# MINI_SAM_D51_019.net
KiCad netlist of a schematic drawn in EAGLE
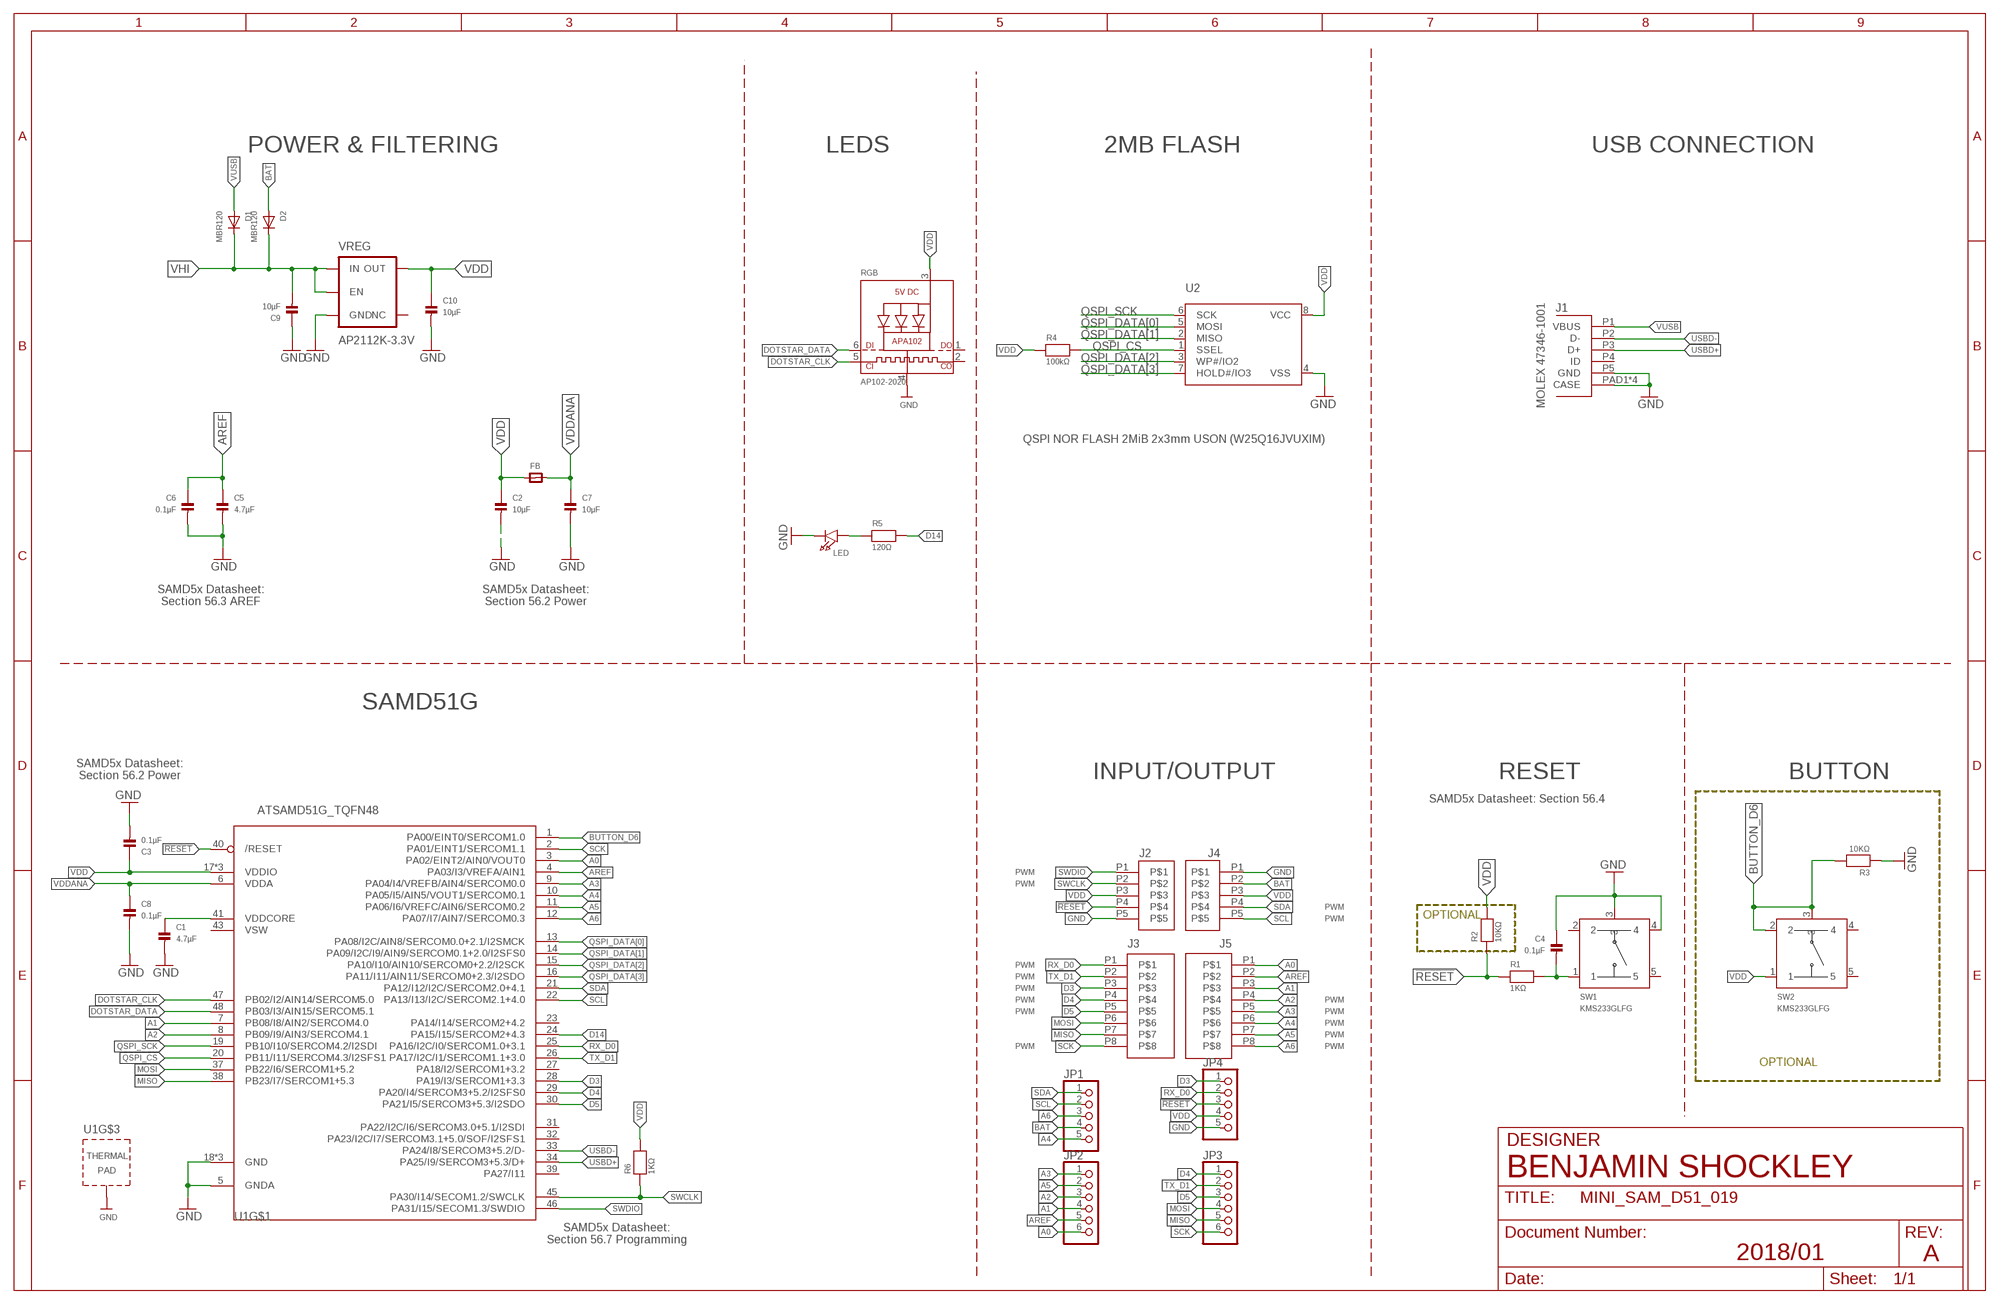
[diagram p0: schematic, sheet 1]

(export (version "E")
  (design (tool "Eeschema 10.0.6"))
  (components
    (comp (ref "C1")
      (value "4.7µF")
      (footprint "eagle-import:_0603MP")
      (libsource (lib "eagle-import") (part "CAP_CERAMIC_0603MP"))
    )
    (comp (ref "C2")
      (value "10µF")
      (footprint "eagle-import:_0603MP")
      (libsource (lib "eagle-import") (part "CAP_CERAMIC_0603MP"))
    )
    (comp (ref "C3")
      (value "0.1µF")
      (footprint "eagle-import:_0603MP")
      (libsource (lib "eagle-import") (part "CAP_CERAMIC_0603MP"))
    )
    (comp (ref "C4")
      (value "0.1µF")
      (footprint "eagle-import:_0603MP")
      (libsource (lib "eagle-import") (part "CAP_CERAMIC_0603MP"))
    )
    (comp (ref "C5")
      (value "4.7µF")
      (footprint "eagle-import:_0603MP")
      (libsource (lib "eagle-import") (part "CAP_CERAMIC_0603MP"))
    )
    (comp (ref "C6")
      (value "0.1µF")
      (footprint "eagle-import:_0603MP")
      (libsource (lib "eagle-import") (part "CAP_CERAMIC_0603MP"))
    )
    (comp (ref "C7")
      (value "10µF")
      (footprint "eagle-import:_0603MP")
      (libsource (lib "eagle-import") (part "CAP_CERAMIC_0603MP"))
    )
    (comp (ref "C8")
      (value "0.1µF")
      (footprint "eagle-import:_0603MP")
      (libsource (lib "eagle-import") (part "CAP_CERAMIC_0603MP"))
    )
    (comp (ref "C9")
      (value "10µF")
      (footprint "eagle-import:_0603MP")
      (libsource (lib "eagle-import") (part "CAP_CERAMIC_0603MP"))
    )
    (comp (ref "C10")
      (value "10µF")
      (footprint "eagle-import:_0603MP")
      (libsource (lib "eagle-import") (part "CAP_CERAMIC_0603MP"))
    )
    (comp (ref "D1")
      (value "MBR120")
      (footprint "eagle-import:SOD-123FL")
      (libsource (lib "eagle-import") (part "DIODE_SOD-123FL"))
    )
    (comp (ref "D2")
      (value "MBR120")
      (footprint "eagle-import:SOD-123FL")
      (libsource (lib "eagle-import") (part "DIODE_SOD-123FL"))
    )
    (comp (ref "FB")
      (value "Impedence: 50 ohm @ 20 MHz, 220 Ohm @ 100 MHz; low DC resistance")
      (footprint "eagle-import:_0603MP")
      (libsource (lib "eagle-import") (part "FERRITE_0603MP"))
    )
    (comp (ref "J1")
      (value "MOLEX_47346-100147346")
      (footprint "eagle-import:MOLEX_47346-1001")
      (libsource (lib "eagle-import") (part "MOLEX_47346-100147346"))
    )
    (comp (ref "J2")
      (value "1X5_HEADER_1.27MMCAST")
      (footprint "eagle-import:1X5_HEADER_1.27MM_CASTELLATED")
      (libsource (lib "eagle-import") (part "1X5_HEADER_1.27MMCAST"))
    )
    (comp (ref "J3")
      (value "1X8_HEADER_1.27MMCAST")
      (footprint "eagle-import:1X8_HEADER_1.27MM_CASTELLATED")
      (libsource (lib "eagle-import") (part "1X8_HEADER_1.27MMCAST"))
    )
    (comp (ref "J4")
      (value "1X5_HEADER_1.27MMCAST")
      (footprint "eagle-import:1X5_HEADER_1.27MM_CASTELLATED")
      (libsource (lib "eagle-import") (part "1X5_HEADER_1.27MMCAST"))
    )
    (comp (ref "J5")
      (value "1X8_HEADER_1.27MMCAST")
      (footprint "eagle-import:1X8_HEADER_1.27MM_CASTELLATED")
      (libsource (lib "eagle-import") (part "1X8_HEADER_1.27MMCAST"))
    )
    (comp (ref "JP1")
      (value "PINHD-1X51X05_SMT")
      (footprint "eagle-import:1X05_SMT")
      (libsource (lib "eagle-import") (part "PINHD-1X51X05_SMT"))
    )
    (comp (ref "JP2")
      (value "PINHD-1X61X06_SMT")
      (footprint "eagle-import:1X06_SMT")
      (libsource (lib "eagle-import") (part "PINHD-1X61X06_SMT"))
    )
    (comp (ref "JP3")
      (value "PINHD-1X6REV")
      (footprint "eagle-import:1X06_SMT_REV")
      (libsource (lib "eagle-import") (part "PINHD-1X6REV"))
    )
    (comp (ref "JP4")
      (value "PINHD-1X51X05_SMT")
      (footprint "eagle-import:1X05_SMT")
      (libsource (lib "eagle-import") (part "PINHD-1X51X05_SMT"))
    )
    (comp (ref "LED")
      (value "VLRK31Q1R2-GS08")
      (footprint "eagle-import:REVERSE_MOUNT_LED")
      (libsource (lib "eagle-import") (part "REVERSEMOUNTLED"))
    )
    (comp (ref "R1")
      (value "1KΩ")
      (footprint "eagle-import:_0603MP")
      (libsource (lib "eagle-import") (part "RESISTOR_0603MP"))
    )
    (comp (ref "R2")
      (value "10KΩ")
      (footprint "eagle-import:_0603MP")
      (libsource (lib "eagle-import") (part "RESISTOR_0603MP"))
    )
    (comp (ref "R3")
      (value "10KΩ")
      (footprint "eagle-import:_0603MP")
      (libsource (lib "eagle-import") (part "RESISTOR_0603MP"))
    )
    (comp (ref "R4")
      (value "100kΩ")
      (footprint "eagle-import:_0603MP")
      (libsource (lib "eagle-import") (part "RESISTOR_0603MP"))
    )
    (comp (ref "R5")
      (value "120Ω")
      (footprint "eagle-import:_0603MP")
      (libsource (lib "eagle-import") (part "RESISTOR_0603MP"))
    )
    (comp (ref "R6")
      (value "1KΩ")
      (footprint "eagle-import:_0603MP")
      (libsource (lib "eagle-import") (part "RESISTOR_0603MP"))
    )
    (comp (ref "RGB")
      (value "AP102-2020")
      (footprint "eagle-import:APA102_2020")
      (libsource (lib "eagle-import") (part "APA1022020"))
    )
    (comp (ref "SW1")
      (value "KMS233GLFG")
      (footprint "eagle-import:KMS_SWITCH")
      (libsource (lib "eagle-import") (part "KMS_SWITCHKMS"))
    )
    (comp (ref "SW2")
      (value "KMS233GLFG")
      (footprint "eagle-import:KMS_SWITCH")
      (libsource (lib "eagle-import") (part "KMS_SWITCHKMS"))
    )
    (comp (ref "U1")
      (value "ATSAMD51G_TQFN48")
      (footprint "eagle-import:TQFN48_7MM")
      (libsource (lib "eagle-import") (part "ATSAMD51G_TQFN48"))
    )
    (comp (ref "U2")
      (value "QSPI NOR FLASH 2MiB 2x3mm USON (W25Q16JVUXIM)")
      (footprint "eagle-import:USON8")
      (libsource (lib "eagle-import") (part "SPIFLASH_8PINUX"))
    )
    (comp (ref "VREG")
      (value "AP2112K-3.3V")
      (footprint "eagle-import:SOT23-5")
      (libsource (lib "eagle-import") (part "V_REG_AP2112K-3.3V"))
    )
  )
  (nets
    (net (code "1") (name "/VSW") (class "Default")
      (node (ref "U1") (pin "43") (pinfunction "VSW_43") (pintype "power_in"))
    )
    (net (code "2") (name "/~{RESET}") (class "Default")
      (node (ref "J2") (pin "P4") (pinfunction "P$4_P4") (pintype "bidirectional"))
      (node (ref "JP4") (pin "3") (pinfunction "3_3") (pintype "passive"))
      (node (ref "R1") (pin "1") (pinfunction "1_1") (pintype "passive"))
      (node (ref "R2") (pin "1") (pinfunction "1_1") (pintype "passive"))
      (node (ref "U1") (pin "40") (pinfunction "/RESET_40") (pintype "bidirectional"))
    )
    (net (code "3") (name "A0") (class "Default")
      (node (ref "J5") (pin "P1") (pinfunction "P$1_P1") (pintype "bidirectional"))
      (node (ref "JP2") (pin "6") (pinfunction "6_6") (pintype "passive"))
      (node (ref "U1") (pin "3") (pinfunction "PA02/EINT2/AIN0/VOUT0_3") (pintype "bidirectional"))
    )
    (net (code "4") (name "A1") (class "Default")
      (node (ref "J5") (pin "P3") (pinfunction "P$3_P3") (pintype "bidirectional"))
      (node (ref "JP2") (pin "4") (pinfunction "4_4") (pintype "passive"))
      (node (ref "U1") (pin "7") (pinfunction "PB08/I8/AIN2/SERCOM4.0_7") (pintype "bidirectional"))
    )
    (net (code "5") (name "A2") (class "Default")
      (node (ref "J5") (pin "P4") (pinfunction "P$4_P4") (pintype "bidirectional"))
      (node (ref "JP2") (pin "3") (pinfunction "3_3") (pintype "passive"))
      (node (ref "U1") (pin "8") (pinfunction "PB09/I9/AIN3/SERCOM4.1_8") (pintype "bidirectional"))
    )
    (net (code "6") (name "A3") (class "Default")
      (node (ref "J5") (pin "P5") (pinfunction "P$5_P5") (pintype "bidirectional"))
      (node (ref "JP2") (pin "1") (pinfunction "1_1") (pintype "passive"))
      (node (ref "U1") (pin "9") (pinfunction "PA04/I4/VREFB/AIN4/SERCOM0.0_9") (pintype "bidirectional"))
    )
    (net (code "7") (name "A4") (class "Default")
      (node (ref "J5") (pin "P6") (pinfunction "P$6_P6") (pintype "bidirectional"))
      (node (ref "JP1") (pin "5") (pinfunction "5_5") (pintype "passive"))
      (node (ref "U1") (pin "10") (pinfunction "PA05/I5/AIN5/VOUT1/SERCOM0.1_10") (pintype "bidirectional"))
    )
    (net (code "8") (name "A5") (class "Default")
      (node (ref "J5") (pin "P7") (pinfunction "P$7_P7") (pintype "bidirectional"))
      (node (ref "JP2") (pin "2") (pinfunction "2_2") (pintype "passive"))
      (node (ref "U1") (pin "11") (pinfunction "PA06/I6/VREFC/AIN6/SERCOM0.2_11") (pintype "bidirectional"))
    )
    (net (code "9") (name "A6") (class "Default")
      (node (ref "J5") (pin "P8") (pinfunction "P$8_P8") (pintype "bidirectional"))
      (node (ref "JP1") (pin "3") (pinfunction "3_3") (pintype "passive"))
      (node (ref "U1") (pin "12") (pinfunction "PA07/I7/AIN7/SERCOM0.3_12") (pintype "bidirectional"))
    )
    (net (code "10") (name "AREF") (class "Default")
      (node (ref "C5") (pin "1") (pinfunction "P$1_1") (pintype "passive"))
      (node (ref "C6") (pin "1") (pinfunction "P$1_1") (pintype "passive"))
      (node (ref "J5") (pin "P2") (pinfunction "P$2_P2") (pintype "bidirectional"))
      (node (ref "JP2") (pin "5") (pinfunction "5_5") (pintype "passive"))
      (node (ref "U1") (pin "4") (pinfunction "PA03/I3/VREFA/AIN1_4") (pintype "bidirectional"))
    )
    (net (code "11") (name "BAT") (class "Default")
      (node (ref "D2") (pin "A") (pinfunction "A_A") (pintype "passive"))
      (node (ref "J4") (pin "P2") (pinfunction "P$2_P2") (pintype "bidirectional"))
      (node (ref "JP1") (pin "4") (pinfunction "4_4") (pintype "passive"))
    )
    (net (code "12") (name "BUTTON_D6") (class "Default")
      (node (ref "R3") (pin "2") (pinfunction "2_2") (pintype "passive"))
      (node (ref "SW2") (pin "2") (pinfunction "2_2") (pintype "bidirectional"))
      (node (ref "SW2") (pin "3") (pinfunction "3_3") (pintype "bidirectional"))
      (node (ref "U1") (pin "1") (pinfunction "PA00/EINT0/SERCOM1.0_1") (pintype "bidirectional"))
    )
    (net (code "13") (name "D3") (class "Default")
      (node (ref "J3") (pin "P3") (pinfunction "P$3_P3") (pintype "bidirectional"))
      (node (ref "JP4") (pin "1") (pinfunction "1_1") (pintype "passive"))
      (node (ref "U1") (pin "28") (pinfunction "PA19/I3/SERCOM1+3.3_28") (pintype "bidirectional"))
    )
    (net (code "14") (name "D4") (class "Default")
      (node (ref "J3") (pin "P4") (pinfunction "P$4_P4") (pintype "bidirectional"))
      (node (ref "JP3") (pin "1") (pinfunction "1_1") (pintype "passive"))
      (node (ref "U1") (pin "29") (pinfunction "PA20/I4/SERCOM3+5.2/I2SFS0_29") (pintype "bidirectional"))
    )
    (net (code "15") (name "D5") (class "Default")
      (node (ref "J3") (pin "P5") (pinfunction "P$5_P5") (pintype "bidirectional"))
      (node (ref "JP3") (pin "3") (pinfunction "3_3") (pintype "passive"))
      (node (ref "U1") (pin "30") (pinfunction "PA21/I5/SERCOM3+5.3/I2SDO_30") (pintype "bidirectional"))
    )
    (net (code "16") (name "D14") (class "Default")
      (node (ref "R5") (pin "2") (pinfunction "2_2") (pintype "passive"))
      (node (ref "U1") (pin "24") (pinfunction "PA15/I15/SERCOM2+4.3_24") (pintype "bidirectional"))
    )
    (net (code "17") (name "DOTSTAR_CLK") (class "Default")
      (node (ref "RGB") (pin "5") (pinfunction "CKI_5") (pintype "input"))
      (node (ref "U1") (pin "47") (pinfunction "PB02/I2/AIN14/SERCOM5.0_47") (pintype "bidirectional"))
    )
    (net (code "18") (name "DOTSTAR_DATA") (class "Default")
      (node (ref "RGB") (pin "6") (pinfunction "DI_6") (pintype "input"))
      (node (ref "U1") (pin "48") (pinfunction "PB03/I3/AIN15/SERCOM5.1_48") (pintype "bidirectional"))
    )
    (net (code "19") (name "GND") (class "Default")
      (node (ref "C1") (pin "2") (pinfunction "P$2_2") (pintype "passive"))
      (node (ref "C10") (pin "2") (pinfunction "P$2_2") (pintype "passive"))
      (node (ref "C2") (pin "2") (pinfunction "P$2_2") (pintype "passive"))
      (node (ref "C3") (pin "2") (pinfunction "P$2_2") (pintype "passive"))
      (node (ref "C4") (pin "1") (pinfunction "P$1_1") (pintype "passive"))
      (node (ref "C5") (pin "2") (pinfunction "P$2_2") (pintype "passive"))
      (node (ref "C6") (pin "2") (pinfunction "P$2_2") (pintype "passive"))
      (node (ref "C7") (pin "2") (pinfunction "P$2_2") (pintype "passive"))
      (node (ref "C8") (pin "2") (pinfunction "P$2_2") (pintype "passive"))
      (node (ref "C9") (pin "1") (pinfunction "P$1_1") (pintype "passive"))
      (node (ref "J1") (pin "P5") (pinfunction "GND_P5") (pintype "power_in"))
      (node (ref "J1") (pin "PAD1") (pinfunction "CASE_PAD1") (pintype "bidirectional"))
      (node (ref "J1") (pin "PAD2") (pinfunction "CASE_PAD2") (pintype "bidirectional"))
      (node (ref "J1") (pin "PAD3") (pinfunction "CASE_PAD3") (pintype "bidirectional"))
      (node (ref "J1") (pin "PAD4") (pinfunction "CASE_PAD4") (pintype "bidirectional"))
      (node (ref "J2") (pin "P5") (pinfunction "P$5_P5") (pintype "bidirectional"))
      (node (ref "J4") (pin "P1") (pinfunction "P$1_P1") (pintype "bidirectional"))
      (node (ref "JP4") (pin "5") (pinfunction "5_5") (pintype "passive"))
      (node (ref "LED") (pin "C") (pinfunction "C_C") (pintype "passive"))
      (node (ref "R3") (pin "1") (pinfunction "1_1") (pintype "passive"))
      (node (ref "RGB") (pin "4") (pinfunction "GND_4") (pintype "power_in"))
      (node (ref "SW1") (pin "3") (pinfunction "3_3") (pintype "bidirectional"))
      (node (ref "SW1") (pin "4") (pinfunction "4_4") (pintype "bidirectional"))
      (node (ref "U1") (pin "18") (pinfunction "GND_18") (pintype "power_in"))
      (node (ref "U1") (pin "35") (pinfunction "GND_35") (pintype "power_in"))
      (node (ref "U1") (pin "42") (pinfunction "GND_42") (pintype "power_in"))
      (node (ref "U1") (pin "5") (pinfunction "GNDA_5") (pintype "power_in"))
      (node (ref "U1") (pin "THERMAL") (pinfunction "TP_THERMAL") (pintype "power_in"))
      (node (ref "U2") (pin "4") (pinfunction "VSS_4") (pintype "bidirectional"))
      (node (ref "VREG") (pin "2") (pinfunction "GND_2") (pintype "input"))
    )
    (net (code "20") (name "MISO") (class "Default")
      (node (ref "J3") (pin "P7") (pinfunction "P$7_P7") (pintype "bidirectional"))
      (node (ref "JP3") (pin "5") (pinfunction "5_5") (pintype "passive"))
      (node (ref "U1") (pin "38") (pinfunction "PB23/I7/SERCOM1+5.3_38") (pintype "bidirectional"))
    )
    (net (code "21") (name "MOSI") (class "Default")
      (node (ref "J3") (pin "P6") (pinfunction "P$6_P6") (pintype "bidirectional"))
      (node (ref "JP3") (pin "4") (pinfunction "4_4") (pintype "passive"))
      (node (ref "U1") (pin "37") (pinfunction "PB22/I6/SERCOM1+5.2_37") (pintype "bidirectional"))
    )
    (net (code "22") (name "Net-(C1-P$1)") (class "Default")
      (node (ref "C1") (pin "1") (pinfunction "P$1_1") (pintype "passive"))
      (node (ref "U1") (pin "41") (pinfunction "VDDCORE_41") (pintype "power_in"))
    )
    (net (code "23") (name "Net-(C4-P$2)") (class "Default")
      (node (ref "C4") (pin "2") (pinfunction "P$2_2") (pintype "passive"))
      (node (ref "R1") (pin "2") (pinfunction "2_2") (pintype "passive"))
      (node (ref "SW1") (pin "1") (pinfunction "1_1") (pintype "bidirectional"))
    )
    (net (code "24") (name "Net-(LED-PadA)") (class "Default")
      (node (ref "LED") (pin "A") (pinfunction "A_A") (pintype "passive"))
      (node (ref "R5") (pin "1") (pinfunction "1_1") (pintype "passive"))
    )
    (net (code "25") (name "QSPI_CS") (class "Default")
      (node (ref "R4") (pin "2") (pinfunction "2_2") (pintype "passive"))
      (node (ref "U1") (pin "20") (pinfunction "PB11/I11/SERCOM4.3/I2SFS1_20") (pintype "bidirectional"))
      (node (ref "U2") (pin "1") (pinfunction "SSEL_1") (pintype "bidirectional"))
    )
    (net (code "26") (name "QSPI_DATA[0]") (class "Default")
      (node (ref "U1") (pin "13") (pinfunction "PA08/I2C/AIN8/SERCOM0.0+2.1/I2SMCK_13") (pintype "bidirectional"))
      (node (ref "U2") (pin "5") (pinfunction "MOSI_5") (pintype "bidirectional"))
    )
    (net (code "27") (name "QSPI_DATA[1]") (class "Default")
      (node (ref "U1") (pin "14") (pinfunction "PA09/I2C/I9/AIN9/SERCOM0.1+2.0/I2SFS0_14") (pintype "bidirectional"))
      (node (ref "U2") (pin "2") (pinfunction "MISO_2") (pintype "bidirectional"))
    )
    (net (code "28") (name "QSPI_DATA[2]") (class "Default")
      (node (ref "U1") (pin "15") (pinfunction "PA10/I10/AIN10/SERCOM0+2.2/I2SCK_15") (pintype "bidirectional"))
      (node (ref "U2") (pin "3") (pinfunction "WP#/IO2_3") (pintype "bidirectional"))
    )
    (net (code "29") (name "QSPI_DATA[3]") (class "Default")
      (node (ref "U1") (pin "16") (pinfunction "PA11/I11/AIN11/SERCOM0+2.3/I2SDO_16") (pintype "bidirectional"))
      (node (ref "U2") (pin "7") (pinfunction "HOLD#/IO3_7") (pintype "bidirectional"))
    )
    (net (code "30") (name "QSPI_SCK") (class "Default")
      (node (ref "U1") (pin "19") (pinfunction "PB10/I10/SERCOM4.2/I2SDI_19") (pintype "bidirectional"))
      (node (ref "U2") (pin "6") (pinfunction "SCK_6") (pintype "bidirectional"))
    )
    (net (code "31") (name "RX_D0") (class "Default")
      (node (ref "J3") (pin "P1") (pinfunction "P$1_P1") (pintype "bidirectional"))
      (node (ref "JP4") (pin "2") (pinfunction "2_2") (pintype "passive"))
      (node (ref "U1") (pin "25") (pinfunction "PA16/I2C/I0/SERCOM1.0+3.1_25") (pintype "bidirectional"))
    )
    (net (code "32") (name "SCK") (class "Default")
      (node (ref "J3") (pin "P8") (pinfunction "P$8_P8") (pintype "bidirectional"))
      (node (ref "JP3") (pin "6") (pinfunction "6_6") (pintype "passive"))
      (node (ref "U1") (pin "2") (pinfunction "PA01/EINT1/SERCOM1.1_2") (pintype "bidirectional"))
    )
    (net (code "33") (name "SCL") (class "Default")
      (node (ref "J4") (pin "P5") (pinfunction "P$5_P5") (pintype "bidirectional"))
      (node (ref "JP1") (pin "2") (pinfunction "2_2") (pintype "passive"))
      (node (ref "U1") (pin "22") (pinfunction "PA13/I13/I2C/SERCOM2.1+4.0_22") (pintype "bidirectional"))
    )
    (net (code "34") (name "SDA") (class "Default")
      (node (ref "J4") (pin "P4") (pinfunction "P$4_P4") (pintype "bidirectional"))
      (node (ref "JP1") (pin "1") (pinfunction "1_1") (pintype "passive"))
      (node (ref "U1") (pin "21") (pinfunction "PA12/I12/I2C/SERCOM2.0+4.1_21") (pintype "bidirectional"))
    )
    (net (code "35") (name "SWCLK") (class "Default")
      (node (ref "J2") (pin "P2") (pinfunction "P$2_P2") (pintype "bidirectional"))
      (node (ref "R6") (pin "1") (pinfunction "1_1") (pintype "passive"))
      (node (ref "U1") (pin "45") (pinfunction "PA30/I14/SECOM1.2/SWCLK_45") (pintype "bidirectional"))
    )
    (net (code "36") (name "SWDIO") (class "Default")
      (node (ref "J2") (pin "P1") (pinfunction "P$1_P1") (pintype "bidirectional"))
      (node (ref "U1") (pin "46") (pinfunction "PA31/I15/SECOM1.3/SWDIO_46") (pintype "bidirectional"))
    )
    (net (code "37") (name "TX_D1") (class "Default")
      (node (ref "J3") (pin "P2") (pinfunction "P$2_P2") (pintype "bidirectional"))
      (node (ref "JP3") (pin "2") (pinfunction "2_2") (pintype "passive"))
      (node (ref "U1") (pin "26") (pinfunction "PA17/I2C/I1/SERCOM1.1+3.0_26") (pintype "bidirectional"))
    )
    (net (code "38") (name "USBD+") (class "Default")
      (node (ref "J1") (pin "P3") (pinfunction "D+_P3") (pintype "bidirectional"))
      (node (ref "U1") (pin "34") (pinfunction "PA25/I9/SERCOM3+5.3/D+_34") (pintype "bidirectional"))
    )
    (net (code "39") (name "USBD-") (class "Default")
      (node (ref "J1") (pin "P2") (pinfunction "D-_P2") (pintype "bidirectional"))
      (node (ref "U1") (pin "33") (pinfunction "PA24/I8/SERCOM3+5.2/D-_33") (pintype "bidirectional"))
    )
    (net (code "40") (name "VDD") (class "Default")
      (node (ref "C10") (pin "1") (pinfunction "P$1_1") (pintype "passive"))
      (node (ref "C2") (pin "1") (pinfunction "P$1_1") (pintype "passive"))
      (node (ref "C3") (pin "1") (pinfunction "P$1_1") (pintype "passive"))
      (node (ref "FB") (pin "1") (pinfunction "P$1_1") (pintype "passive"))
      (node (ref "J2") (pin "P3") (pinfunction "P$3_P3") (pintype "bidirectional"))
      (node (ref "J4") (pin "P3") (pinfunction "P$3_P3") (pintype "bidirectional"))
      (node (ref "JP4") (pin "4") (pinfunction "4_4") (pintype "passive"))
      (node (ref "R2") (pin "2") (pinfunction "2_2") (pintype "passive"))
      (node (ref "R4") (pin "1") (pinfunction "1_1") (pintype "passive"))
      (node (ref "R6") (pin "2") (pinfunction "2_2") (pintype "passive"))
      (node (ref "RGB") (pin "3") (pinfunction "VDD_3") (pintype "power_in"))
      (node (ref "SW2") (pin "1") (pinfunction "1_1") (pintype "bidirectional"))
      (node (ref "U1") (pin "17") (pinfunction "VDDIO_17") (pintype "power_in"))
      (node (ref "U1") (pin "36") (pinfunction "VDDIO_36") (pintype "power_in"))
      (node (ref "U1") (pin "44") (pinfunction "VDDIO_44") (pintype "power_in"))
      (node (ref "U2") (pin "8") (pinfunction "VCC_8") (pintype "bidirectional"))
      (node (ref "VREG") (pin "5") (pinfunction "OUT_5") (pintype "passive"))
    )
    (net (code "41") (name "VDDANA") (class "Default")
      (node (ref "C7") (pin "1") (pinfunction "P$1_1") (pintype "passive"))
      (node (ref "C8") (pin "1") (pinfunction "P$1_1") (pintype "passive"))
      (node (ref "FB") (pin "2") (pinfunction "P$2_2") (pintype "passive"))
      (node (ref "U1") (pin "6") (pinfunction "VDDA_6") (pintype "power_in"))
    )
    (net (code "42") (name "VHI") (class "Default")
      (node (ref "C9") (pin "2") (pinfunction "P$2_2") (pintype "passive"))
      (node (ref "D1") (pin "C") (pinfunction "C_C") (pintype "passive"))
      (node (ref "D2") (pin "C") (pinfunction "C_C") (pintype "passive"))
      (node (ref "VREG") (pin "1") (pinfunction "IN_1") (pintype "input"))
      (node (ref "VREG") (pin "3") (pinfunction "EN_3") (pintype "input"))
    )
    (net (code "43") (name "VUSB") (class "Default")
      (node (ref "D1") (pin "A") (pinfunction "A_A") (pintype "passive"))
      (node (ref "J1") (pin "P1") (pinfunction "VBUS_P1") (pintype "power_in"))
    )
    (net (code "44") (name "unconnected-(J1-ID-PadP4)") (class "Default")
      (node (ref "J1") (pin "P4") (pinfunction "ID_P4") (pintype "bidirectional"))
    )
    (net (code "45") (name "unconnected-(RGB-CKO-Pad2)") (class "Default")
      (node (ref "RGB") (pin "2") (pinfunction "CKO_2") (pintype "output"))
    )
    (net (code "46") (name "unconnected-(RGB-DO-Pad1)") (class "Default")
      (node (ref "RGB") (pin "1") (pinfunction "DO_1") (pintype "output"))
    )
    (net (code "47") (name "unconnected-(SW1-Pad2)") (class "Default")
      (node (ref "SW1") (pin "2") (pinfunction "2_2") (pintype "bidirectional"))
    )
    (net (code "48") (name "unconnected-(SW1-Pad5)") (class "Default")
      (node (ref "SW1") (pin "5") (pinfunction "5_5") (pintype "bidirectional"))
    )
    (net (code "49") (name "unconnected-(SW2-Pad4)") (class "Default")
      (node (ref "SW2") (pin "4") (pinfunction "4_4") (pintype "bidirectional"))
    )
    (net (code "50") (name "unconnected-(SW2-Pad5)") (class "Default")
      (node (ref "SW2") (pin "5") (pinfunction "5_5") (pintype "bidirectional"))
    )
    (net (code "51") (name "unconnected-(U1A-PA14{slash}I14{slash}SERCOM2+4.2-Pad23)") (class "Default")
      (node (ref "U1") (pin "23") (pinfunction "PA14/I14/SERCOM2+4.2_23") (pintype "bidirectional"))
    )
    (net (code "52") (name "unconnected-(U1A-PA18{slash}I2{slash}SERCOM1+3.2-Pad27)") (class "Default")
      (node (ref "U1") (pin "27") (pinfunction "PA18/I2/SERCOM1+3.2_27") (pintype "bidirectional"))
    )
    (net (code "53") (name "unconnected-(U1A-PA22{slash}I2C{slash}I6{slash}SERCOM3.0+5.1{slash}I2SDI-Pad31)") (class "Default")
      (node (ref "U1") (pin "31") (pinfunction "PA22/I2C/I6/SERCOM3.0+5.1/I2SDI_31") (pintype "bidirectional"))
    )
    (net (code "54") (name "unconnected-(U1A-PA23{slash}I2C{slash}I7{slash}SERCOM3.1+5.0{slash}SOF{slash}I2SFS1-Pad32)") (class "Default")
      (node (ref "U1") (pin "32") (pinfunction "PA23/I2C/I7/SERCOM3.1+5.0/SOF/I2SFS1_32") (pintype "bidirectional"))
    )
    (net (code "55") (name "unconnected-(U1A-PA27{slash}I11-Pad39)") (class "Default")
      (node (ref "U1") (pin "39") (pinfunction "PA27/I11_39") (pintype "bidirectional"))
    )
    (net (code "56") (name "unconnected-(VREG-NC-Pad4)") (class "Default")
      (node (ref "VREG") (pin "4") (pinfunction "NC_4") (pintype "input"))
    )
  )
)
